# SensorBoard.net
KiCad netlist of a schematic drawn in Altium Designer
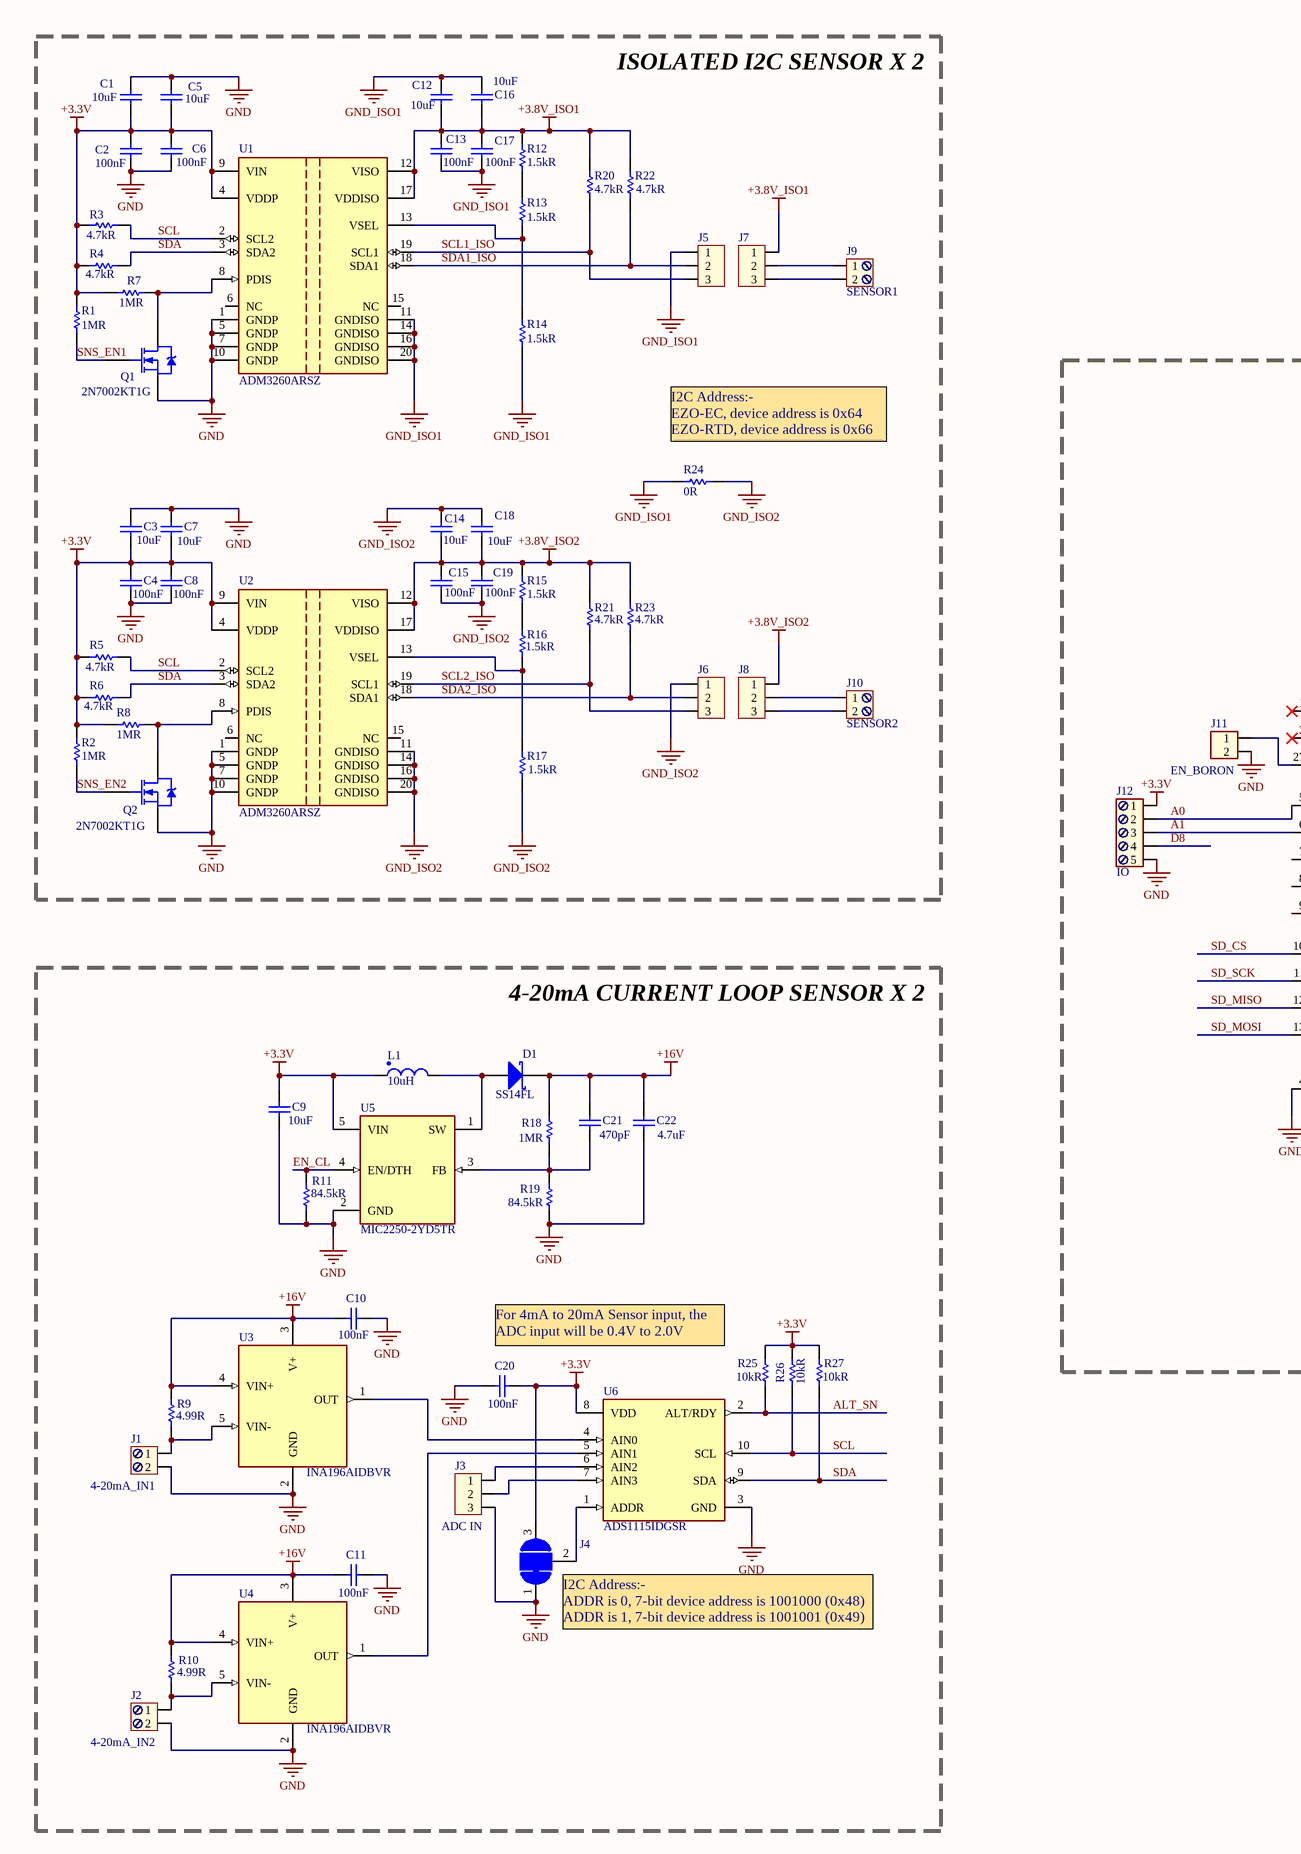
[diagram p0: SensorBoard.SchDoc, left]
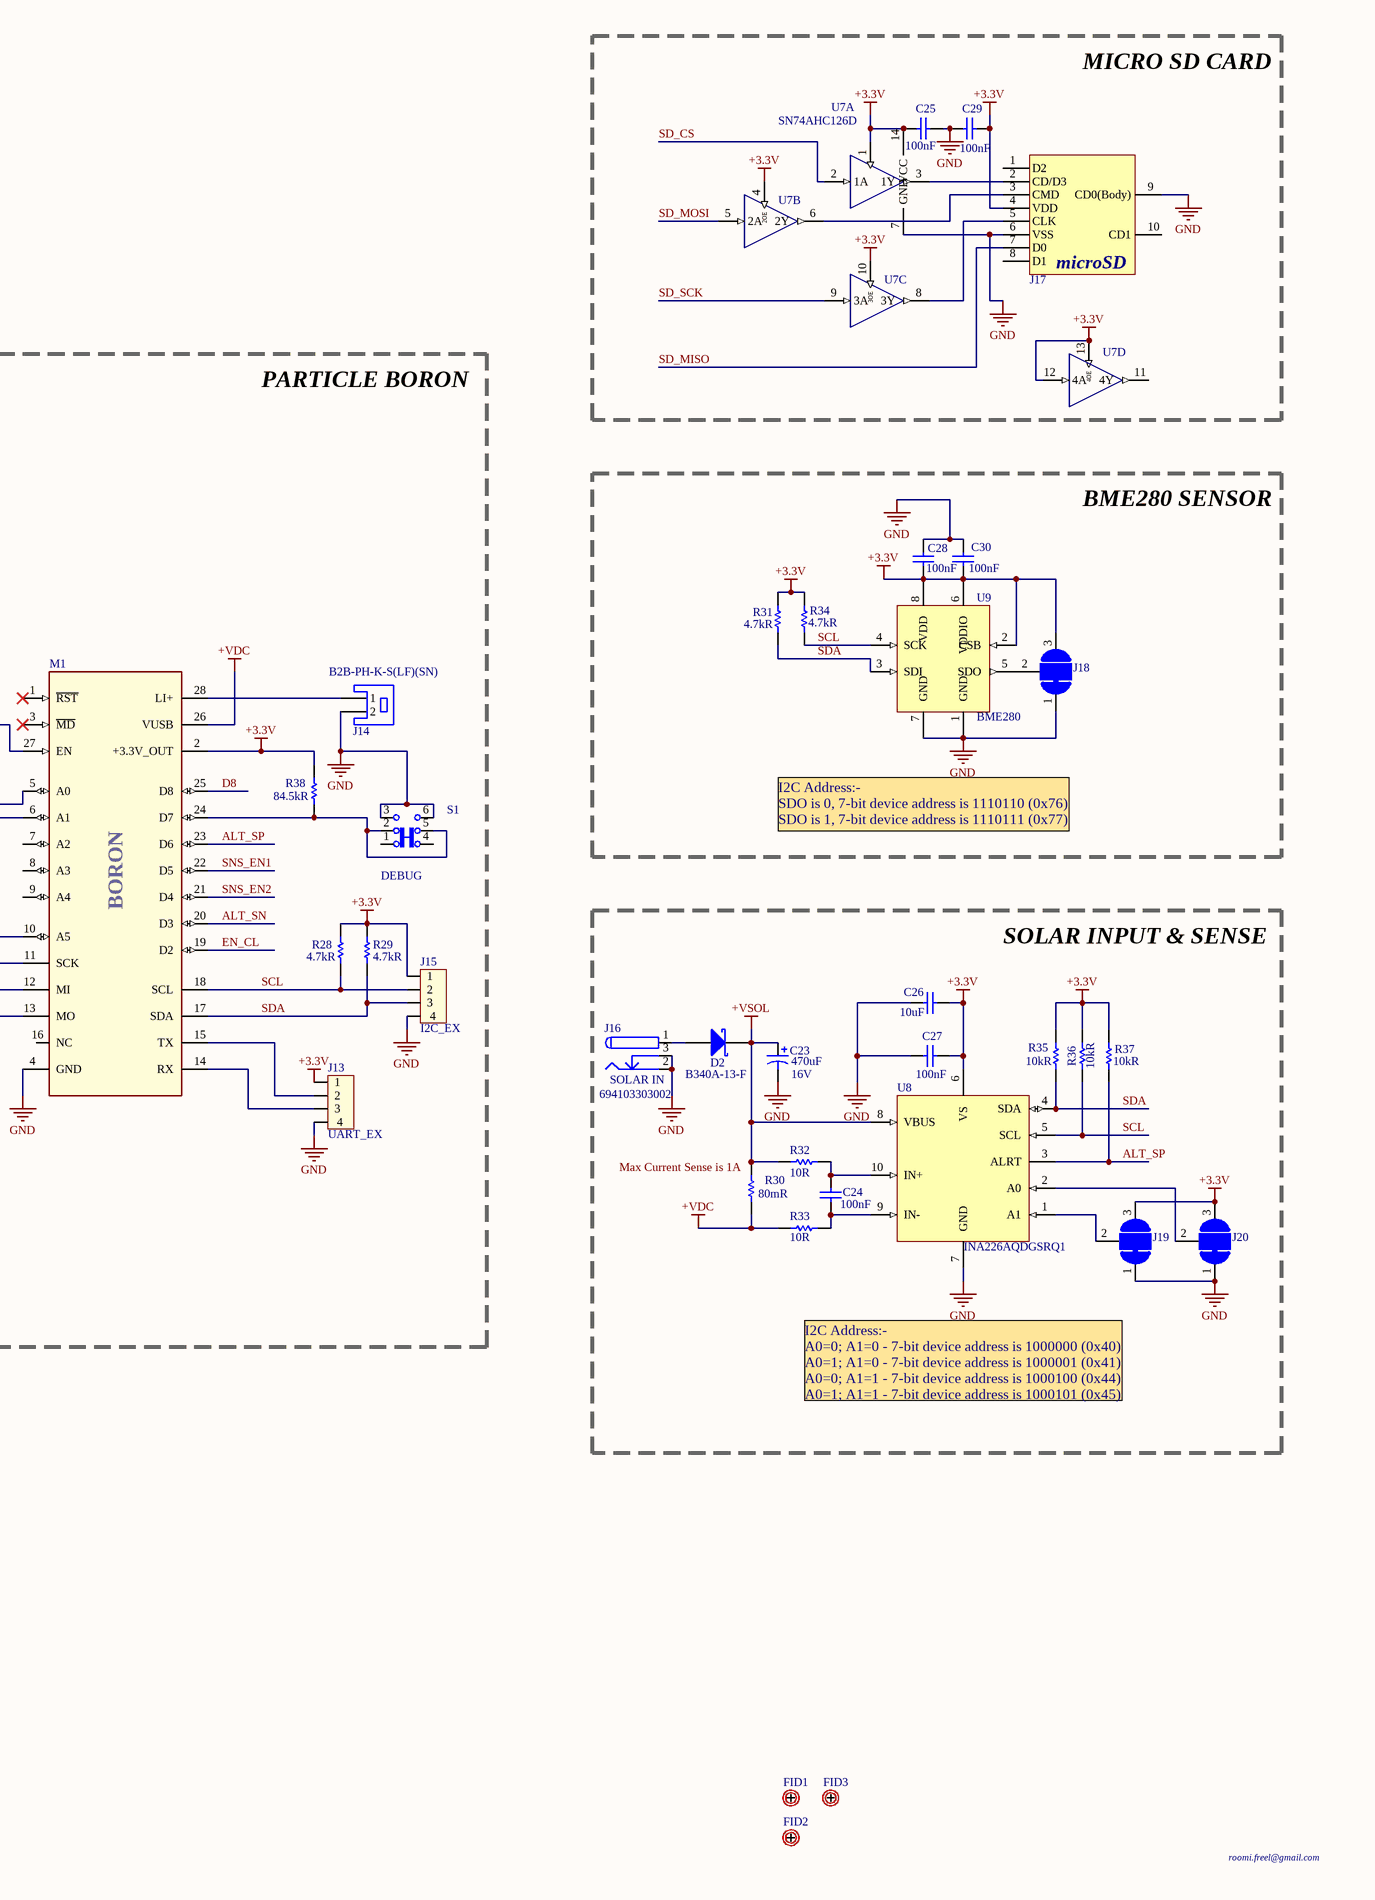
[diagram p1: SensorBoard.SchDoc, right]

(export (version "E")
  (design (tool "Eeschema 10.0.6"))
  (components
    (comp (ref "C1")
      (value "10uF")
      (footprint "C1206")
      (description "Capacitor Non Polar")
      (fields
        (field (name "MANUFACTURER") "Taiyo Yuden")
        (field (name "MANUFACTURER PART NUMBER") "TMK316AB7106KLHT")
        (field (name "CAPACITANCE") "10uF")
      )
      (libsource (lib "RCL_roomi") (part "Capacitor"))
    )
    (comp (ref "C2")
      (value "100nF")
      (footprint "C0805")
      (description "Capacitor Non Polar")
      (fields
        (field (name "MANUFACTURER") "Samsung")
        (field (name "MANUFACTURER PART NUMBER") "CL21B104KCFWPNE")
        (field (name "CAPACITANCE") "100nF")
      )
      (libsource (lib "RCL_roomi") (part "Capacitor"))
    )
    (comp (ref "C3")
      (value "10uF")
      (footprint "C1206")
      (description "Capacitor Non Polar")
      (fields
        (field (name "MANUFACTURER") "Taiyo Yuden")
        (field (name "MANUFACTURER PART NUMBER") "TMK316AB7106KLHT")
        (field (name "CAPACITANCE") "10uF")
      )
      (libsource (lib "RCL_roomi") (part "Capacitor"))
    )
    (comp (ref "C4")
      (value "100nF")
      (footprint "C0805")
      (description "Capacitor Non Polar")
      (fields
        (field (name "MANUFACTURER") "Samsung")
        (field (name "MANUFACTURER PART NUMBER") "CL21B104KCFWPNE")
        (field (name "CAPACITANCE") "100nF")
      )
      (libsource (lib "RCL_roomi") (part "Capacitor"))
    )
    (comp (ref "C5")
      (value "10uF")
      (footprint "C1206")
      (description "Capacitor Non Polar")
      (fields
        (field (name "MANUFACTURER") "Taiyo Yuden")
        (field (name "MANUFACTURER PART NUMBER") "TMK316AB7106KLHT")
        (field (name "CAPACITANCE") "10uF")
      )
      (libsource (lib "RCL_roomi") (part "Capacitor"))
    )
    (comp (ref "C6")
      (value "100nF")
      (footprint "C0805")
      (description "Capacitor Non Polar")
      (fields
        (field (name "MANUFACTURER") "Samsung")
        (field (name "MANUFACTURER PART NUMBER") "CL21B104KCFWPNE")
        (field (name "CAPACITANCE") "100nF")
      )
      (libsource (lib "RCL_roomi") (part "Capacitor"))
    )
    (comp (ref "C7")
      (value "10uF")
      (footprint "C1206")
      (description "Capacitor Non Polar")
      (fields
        (field (name "MANUFACTURER") "Taiyo Yuden")
        (field (name "MANUFACTURER PART NUMBER") "TMK316AB7106KLHT")
        (field (name "CAPACITANCE") "10uF")
      )
      (libsource (lib "RCL_roomi") (part "Capacitor"))
    )
    (comp (ref "C8")
      (value "100nF")
      (footprint "C0805")
      (description "Capacitor Non Polar")
      (fields
        (field (name "MANUFACTURER") "Samsung")
        (field (name "MANUFACTURER PART NUMBER") "CL21B104KCFWPNE")
        (field (name "CAPACITANCE") "100nF")
      )
      (libsource (lib "RCL_roomi") (part "Capacitor"))
    )
    (comp (ref "C9")
      (value "10uF")
      (footprint "C1206")
      (description "Capacitor Non Polar")
      (fields
        (field (name "MANUFACTURER") "Taiyo Yuden")
        (field (name "MANUFACTURER PART NUMBER") "TMK316AB7106KLHT")
        (field (name "CAPACITANCE") "10uF")
      )
      (libsource (lib "RCL_roomi") (part "Capacitor"))
    )
    (comp (ref "C10")
      (value "100nF")
      (footprint "C0805")
      (description "Capacitor Non Polar")
      (fields
        (field (name "MANUFACTURER") "Samsung")
        (field (name "MANUFACTURER PART NUMBER") "CL21B104KCFWPNE")
        (field (name "CAPACITANCE") "100nF")
      )
      (libsource (lib "RCL_roomi") (part "Capacitor"))
    )
    (comp (ref "C11")
      (value "100nF")
      (footprint "C0805")
      (description "Capacitor Non Polar")
      (fields
        (field (name "MANUFACTURER") "Samsung")
        (field (name "MANUFACTURER PART NUMBER") "CL21B104KCFWPNE")
        (field (name "CAPACITANCE") "100nF")
      )
      (libsource (lib "RCL_roomi") (part "Capacitor"))
    )
    (comp (ref "C12")
      (value "10uF")
      (footprint "C1206")
      (description "Capacitor Non Polar")
      (fields
        (field (name "MANUFACTURER") "Taiyo Yuden")
        (field (name "MANUFACTURER PART NUMBER") "TMK316AB7106KLHT")
        (field (name "CAPACITANCE") "10uF")
      )
      (libsource (lib "RCL_roomi") (part "Capacitor"))
    )
    (comp (ref "C13")
      (value "100nF")
      (footprint "C0805")
      (description "Capacitor Non Polar")
      (fields
        (field (name "MANUFACTURER") "Samsung")
        (field (name "MANUFACTURER PART NUMBER") "CL21B104KCFWPNE")
        (field (name "CAPACITANCE") "100nF")
      )
      (libsource (lib "RCL_roomi") (part "Capacitor"))
    )
    (comp (ref "C14")
      (value "10uF")
      (footprint "C1206")
      (description "Capacitor Non Polar")
      (fields
        (field (name "MANUFACTURER") "Taiyo Yuden")
        (field (name "MANUFACTURER PART NUMBER") "TMK316AB7106KLHT")
        (field (name "CAPACITANCE") "10uF")
      )
      (libsource (lib "RCL_roomi") (part "Capacitor"))
    )
    (comp (ref "C15")
      (value "100nF")
      (footprint "C0805")
      (description "Capacitor Non Polar")
      (fields
        (field (name "MANUFACTURER") "Samsung")
        (field (name "MANUFACTURER PART NUMBER") "CL21B104KCFWPNE")
        (field (name "CAPACITANCE") "100nF")
      )
      (libsource (lib "RCL_roomi") (part "Capacitor"))
    )
    (comp (ref "C16")
      (value "10uF")
      (footprint "C1206")
      (description "Capacitor Non Polar")
      (fields
        (field (name "MANUFACTURER") "Taiyo Yuden")
        (field (name "MANUFACTURER PART NUMBER") "TMK316AB7106KLHT")
        (field (name "CAPACITANCE") "10uF")
      )
      (libsource (lib "RCL_roomi") (part "Capacitor"))
    )
    (comp (ref "C17")
      (value "100nF")
      (footprint "C0805")
      (description "Capacitor Non Polar")
      (fields
        (field (name "MANUFACTURER") "Samsung")
        (field (name "MANUFACTURER PART NUMBER") "CL21B104KCFWPNE")
        (field (name "CAPACITANCE") "100nF")
      )
      (libsource (lib "RCL_roomi") (part "Capacitor"))
    )
    (comp (ref "C18")
      (value "10uF")
      (footprint "C1206")
      (description "Capacitor Non Polar")
      (fields
        (field (name "MANUFACTURER") "Taiyo Yuden")
        (field (name "MANUFACTURER PART NUMBER") "TMK316AB7106KLHT")
        (field (name "CAPACITANCE") "10uF")
      )
      (libsource (lib "RCL_roomi") (part "Capacitor"))
    )
    (comp (ref "C19")
      (value "100nF")
      (footprint "C0805")
      (description "Capacitor Non Polar")
      (fields
        (field (name "MANUFACTURER") "Samsung")
        (field (name "MANUFACTURER PART NUMBER") "CL21B104KCFWPNE")
        (field (name "CAPACITANCE") "100nF")
      )
      (libsource (lib "RCL_roomi") (part "Capacitor"))
    )
    (comp (ref "C20")
      (value "100nF")
      (footprint "C0805")
      (description "Capacitor Non Polar")
      (fields
        (field (name "MANUFACTURER") "Samsung")
        (field (name "MANUFACTURER PART NUMBER") "CL21B104KCFWPNE")
        (field (name "CAPACITANCE") "100nF")
      )
      (libsource (lib "RCL_roomi") (part "Capacitor"))
    )
    (comp (ref "C21")
      (value "470pF")
      (footprint "C0805")
      (description "Capacitor Non Polar")
      (fields
        (field (name "MANUFACTURER") "Samsung")
        (field (name "MANUFACTURER PART NUMBER") "CL21B471KC6WPNC")
        (field (name "CAPACITANCE") "470pF")
      )
      (libsource (lib "RCL_roomi") (part "Capacitor"))
    )
    (comp (ref "C22")
      (value "4.7uF")
      (footprint "C1206")
      (description "Capacitor Non Polar")
      (fields
        (field (name "MANUFACTURER") "Murata")
        (field (name "MANUFACTURER PART NUMBER") "GCJ31CR71E475KA12L")
        (field (name "CAPACITANCE") "4.7uF")
      )
      (libsource (lib "RCL_roomi") (part "Capacitor"))
    )
    (comp (ref "C23")
      (value "470uF")
      (footprint "CAPAE120103X102N")
      (description "Capacitor Polar")
      (fields
        (field (name "MANUFACTURER") "Panasonic")
        (field (name "MANUFACTURER PART NUMBER") "EEEHC1C471P")
        (field (name "CAPACITANCE") "470uF")
        (field (name "VOLTAGE RATING (DC)") "16V")
      )
      (libsource (lib "RCL_roomi") (part "Capacitor-Pol"))
    )
    (comp (ref "C24")
      (value "100nF")
      (footprint "C0805")
      (description "Ceramic Chip Capacitor")
      (fields
        (field (name "MANUFACTURER") "Samsung")
        (field (name "MANUFACTURER PART NUMBER") "CL21B104KCFWPNE")
        (field (name "CAPACITANCE") "100nF")
      )
      (libsource (lib "RCL_roomi") (part "Capacitor"))
    )
    (comp (ref "C25")
      (value "100nF")
      (footprint "C0805")
      (description "Capacitor Non Polar")
      (fields
        (field (name "MANUFACTURER") "Samsung")
        (field (name "MANUFACTURER PART NUMBER") "CL21B104KCFWPNE")
        (field (name "CAPACITANCE") "100nF")
      )
      (libsource (lib "RCL_roomi") (part "Capacitor"))
    )
    (comp (ref "C26")
      (value "10uF")
      (footprint "C1206")
      (description "Ceramic Chip Capacitor")
      (fields
        (field (name "MANUFACTURER") "Taiyo Yuden")
        (field (name "MANUFACTURER PART NUMBER") "TMK316AB7106KLHT")
        (field (name "CAPACITANCE") "10uF")
      )
      (libsource (lib "RCL_roomi") (part "Capacitor"))
    )
    (comp (ref "C27")
      (value "100nF")
      (footprint "C0805")
      (description "Ceramic Chip Capacitor")
      (fields
        (field (name "MANUFACTURER") "Samsung")
        (field (name "MANUFACTURER PART NUMBER") "CL21B104KCFWPNE")
        (field (name "CAPACITANCE") "100nF")
      )
      (libsource (lib "RCL_roomi") (part "Capacitor"))
    )
    (comp (ref "C28")
      (value "100nF")
      (footprint "C0805")
      (description "Capacitor Non Polar")
      (fields
        (field (name "MANUFACTURER") "Samsung")
        (field (name "MANUFACTURER PART NUMBER") "CL21B104KCFWPNE")
        (field (name "CAPACITANCE") "100nF")
      )
      (libsource (lib "RCL_roomi") (part "Capacitor"))
    )
    (comp (ref "C29")
      (value "100nF")
      (footprint "C0805")
      (description "Capacitor Non Polar")
      (fields
        (field (name "MANUFACTURER") "Samsung")
        (field (name "MANUFACTURER PART NUMBER") "CL21B104KCFWPNE")
        (field (name "CAPACITANCE") "100nF")
      )
      (libsource (lib "RCL_roomi") (part "Capacitor"))
    )
    (comp (ref "C30")
      (value "100nF")
      (footprint "C0805")
      (description "Capacitor Non Polar")
      (fields
        (field (name "MANUFACTURER") "Samsung")
        (field (name "MANUFACTURER PART NUMBER") "CL21B104KCFWPNE")
        (field (name "CAPACITANCE") "100nF")
      )
      (libsource (lib "RCL_roomi") (part "Capacitor"))
    )
    (comp (ref "D1")
      (value "Diode_Schottky")
      (footprint "SOD-123F")
      (fields
        (field (name "MANUFACTURER") "ON Semiconductor / Fairchild")
        (field (name "MANUFACTURER PART NUMBER") "SS14FL")
      )
      (libsource (lib "Diodes_roomi") (part "Diode_Schottky"))
    )
    (comp (ref "D2")
      (value "Diode_Schottky")
      (footprint "SMA (DO-214AC)")
      (fields
        (field (name "MANUFACTURER") "Diodes")
        (field (name "MANUFACTURER PART NUMBER") "B340A-13-F")
        (field (name "VOLTAGE") "40V")
      )
      (libsource (lib "Diodes_roomi") (part "Diode_Schottky"))
    )
    (comp (ref "FID1")
      (value "Fiducials")
      (footprint "FID_Round")
      (description "Alignment mark for the pick & place machine")
      (libsource (lib "Misc_roomi") (part "Fiducials"))
    )
    (comp (ref "FID2")
      (value "Fiducials")
      (footprint "FID_Round")
      (description "Alignment mark for the pick & place machine")
      (libsource (lib "Misc_roomi") (part "Fiducials"))
    )
    (comp (ref "FID3")
      (value "Fiducials")
      (footprint "FID_Round")
      (description "Alignment mark for the pick & place machine")
      (libsource (lib "Misc_roomi") (part "Fiducials"))
    )
    (comp (ref "J1")
      (value "4-20mA_IN1")
      (footprint "TB-2P-5.08mm")
      (description "Terminal Block 2 position")
      (fields
        (field (name "MANUFACTURER") "Phoenix Contact")
        (field (name "MANUFACTURER PART NUMBER") "1729128")
      )
      (libsource (lib "Con_roomi") (part "TERM_BLK-2P"))
    )
    (comp (ref "J2")
      (value "4-20mA_IN2")
      (footprint "TB-2P-5.08mm")
      (description "Terminal Block 2 position")
      (fields
        (field (name "MANUFACTURER") "Phoenix Contact")
        (field (name "MANUFACTURER PART NUMBER") "1729128")
      )
      (libsource (lib "Con_roomi") (part "TERM_BLK-2P"))
    )
    (comp (ref "J3")
      (value "ADC IN")
      (footprint "TH,POS-3S, 2.54mm")
      (description "HEADER 1X3")
      (libsource (lib "Con_roomi") (part "HDR 1X3"))
    )
    (comp (ref "J4")
      (value "Jumper 3 Pins Normally Closed")
      (footprint "Jumper3P -NC")
      (libsource (lib "Misc_roomi") (part "Jumper-3P_NC"))
    )
    (comp (ref "J5")
      (value "HDR 1X3")
      (footprint "TH,POS-3S,RCPTCL, 2.54mm")
      (description "HEADER 1X3")
      (fields
        (field (name "MANUFACTURER") "Sullins")
        (field (name "MANUFACTURER PART NUMBER") "PPPC031LFBN-RC")
      )
      (libsource (lib "") (part "HDR 1X3_1"))
    )
    (comp (ref "J6")
      (value "HDR 1X3")
      (footprint "TH,POS-3S,RCPTCL, 2.54mm")
      (description "HEADER 1X3")
      (fields
        (field (name "MANUFACTURER") "Sullins")
        (field (name "MANUFACTURER PART NUMBER") "PPPC031LFBN-RC")
      )
      (libsource (lib "") (part "HDR 1X3_1"))
    )
    (comp (ref "J7")
      (value "HDR 1X3")
      (footprint "TH,POS-3S,RCPTCL, 2.54mm")
      (description "HEADER 1X3")
      (fields
        (field (name "MANUFACTURER") "Sullins")
        (field (name "MANUFACTURER PART NUMBER") "PPPC031LFBN-RC")
      )
      (libsource (lib "Con_roomi") (part "HDR 1X3"))
    )
    (comp (ref "J8")
      (value "HDR 1X3")
      (footprint "TH,POS-3S,RCPTCL, 2.54mm")
      (description "HEADER 1X3")
      (fields
        (field (name "MANUFACTURER") "Sullins")
        (field (name "MANUFACTURER PART NUMBER") "PPPC031LFBN-RC")
      )
      (libsource (lib "Con_roomi") (part "HDR 1X3"))
    )
    (comp (ref "J9")
      (value "SENSOR1")
      (footprint "TB-2P-5.08mm")
      (description "Terminal Block 2 position")
      (fields
        (field (name "MANUFACTURER") "Phoenix Contact")
        (field (name "MANUFACTURER PART NUMBER") "1729128")
      )
      (libsource (lib "") (part "TERM_BLK-2P_1"))
    )
    (comp (ref "J10")
      (value "SENSOR2")
      (footprint "TB-2P-5.08mm")
      (description "Terminal Block 2 position")
      (fields
        (field (name "MANUFACTURER") "Phoenix Contact")
        (field (name "MANUFACTURER PART NUMBER") "1729128")
      )
      (libsource (lib "") (part "TERM_BLK-2P_1"))
    )
    (comp (ref "J11")
      (value "EN_BORON")
      (footprint "TH,POS-2S, 2.54mm")
      (description "HEADER 1X2")
      (libsource (lib "Con_roomi") (part "HDR 1X2"))
    )
    (comp (ref "J12")
      (value "IO")
      (footprint "TB-5P-5.08mm")
      (description "Terminal Block 5 position")
      (fields
        (field (name "MANUFACTURER") "Phoenix Contact")
        (field (name "MANUFACTURER PART NUMBER") "1729157")
      )
      (libsource (lib "Con_roomi") (part "TERM_BLK-5P"))
    )
    (comp (ref "J13")
      (value "UART_EX")
      (footprint "TH,POS-4S, 2.54mm")
      (description "HEADER 1X4")
      (libsource (lib "Con_roomi") (part "HDR 1X4"))
    )
    (comp (ref "J14")
      (value "JST-2P")
      (footprint "JST-2P TH V/T 2.0mm")
      (description "JST 2 Pin, Shrouded Connector")
      (fields
        (field (name "MANUFACTURER") "JST")
        (field (name "MANUFACTURER PART NUMBER") "B2B-PH-K-S(LF)(SN)")
      )
      (libsource (lib "Con_roomi") (part "JST-2P"))
    )
    (comp (ref "J15")
      (value "I2C_EX")
      (footprint "TH,POS-4S, 2.54mm")
      (description "HEADER 1X4")
      (libsource (lib "Con_roomi") (part "HDR 1X4"))
    )
    (comp (ref "J16")
      (value "SOLAR IN")
      (footprint "PWR_JACK_1.1x3.5mm")
      (description "DC Barrel Jack Connector Male")
      (fields
        (field (name "MANUFACTURER") "Wurth Electronics")
        (field (name "MANUFACTURER PART NUMBER") "694103303002")
      )
      (libsource (lib "Con_roomi") (part "Barrel Jack"))
    )
    (comp (ref "J17")
      (value "MicroSD")
      (footprint "MicroSD_H-10")
      (description "MicroSD Connector")
      (fields (field (name "MANUFACTURER") "Hirose") (field (name "MANUFACTURER PART NUMBER") "DM3CS-SF"))
      (libsource (lib "Con_roomi") (part "MicroSD"))
    )
    (comp (ref "J18")
      (value "Jumper 3 Pins Normally Closed")
      (footprint "Jumper3P -NC")
      (libsource (lib "") (part "Jumper-3P_NC_1"))
    )
    (comp (ref "J19")
      (value "Jumper 3 Pins Normally Closed")
      (footprint "Jumper3P -NC")
      (libsource (lib "") (part "Jumper-3P_NC_1"))
    )
    (comp (ref "J20")
      (value "Jumper 3 Pins Normally Closed")
      (footprint "Jumper3P -NC")
      (libsource (lib "") (part "Jumper-3P_NC_1"))
    )
    (comp (ref "L1")
      (value "10uH")
      (footprint "INDP5050X40L")
      (description "Generic Inductor")
      (fields
        (field (name "MANUFACTURER") "Taiyo Yuden")
        (field (name "MANUFACTURER PART NUMBER") "NR5040T100M")
        (field (name "INDUCTANCE") "10uH")
      )
      (libsource (lib "RCL_roomi") (part "Inductor"))
    )
    (comp (ref "M1")
      (value "Particle")
      (footprint "Particle Module")
      (description "Particle BORON, ARGON and XENON Module")
      (fields (field (name "MANUFACTURER PART NUMBER") "BORON"))
      (libsource (lib "Modules_Roomi") (part "Particle"))
    )
    (comp (ref "Q1")
      (value "2N7002")
      (footprint "SOT23")
      (description "N-Channel Power MOSFET with Diode")
      (fields
        (field (name "MANUFACTURER") "ON Semiconductor")
        (field (name "MANUFACTURER PART NUMBER") "2N7002KT1G")
      )
      (libsource (lib "Transistors_roomi") (part "MOSFET-N_D"))
    )
    (comp (ref "Q2")
      (value "2N7002")
      (footprint "SOT23")
      (description "N-Channel Power MOSFET with Diode")
      (fields
        (field (name "MANUFACTURER") "ON Semiconductor")
        (field (name "MANUFACTURER PART NUMBER") "2N7002KT1G")
      )
      (libsource (lib "Transistors_roomi") (part "MOSFET-N_D"))
    )
    (comp (ref "R1")
      (value "1MR")
      (footprint "R0805")
      (description "Generic Resistor")
      (fields
        (field (name "MANUFACTURER") "Yageo")
        (field (name "MANUFACTURER PART NUMBER") "AC0805FR-071ML")
        (field (name "RESISTANCE") "1MR")
      )
      (libsource (lib "RCL_roomi") (part "Resistor"))
    )
    (comp (ref "R2")
      (value "1MR")
      (footprint "R0805")
      (description "Generic Resistor")
      (fields
        (field (name "MANUFACTURER") "Yageo")
        (field (name "MANUFACTURER PART NUMBER") "AC0805FR-071ML")
        (field (name "RESISTANCE") "1MR")
      )
      (libsource (lib "RCL_roomi") (part "Resistor"))
    )
    (comp (ref "R3")
      (value "4.7kR")
      (footprint "R0805")
      (description "Generic Resistor")
      (fields
        (field (name "MANUFACTURER") "Yageo")
        (field (name "MANUFACTURER PART NUMBER") "AC0805FR-074K7L")
        (field (name "RESISTANCE") "4.7kR")
      )
      (libsource (lib "RCL_roomi") (part "Resistor"))
    )
    (comp (ref "R4")
      (value "4.7kR")
      (footprint "R0805")
      (description "Generic Resistor")
      (fields
        (field (name "MANUFACTURER") "Yageo")
        (field (name "MANUFACTURER PART NUMBER") "AC0805FR-074K7L")
        (field (name "RESISTANCE") "4.7kR")
      )
      (libsource (lib "RCL_roomi") (part "Resistor"))
    )
    (comp (ref "R5")
      (value "4.7kR")
      (footprint "R0805")
      (description "Generic Resistor")
      (fields
        (field (name "MANUFACTURER") "Yageo")
        (field (name "MANUFACTURER PART NUMBER") "AC0805FR-074K7L")
        (field (name "RESISTANCE") "4.7kR")
      )
      (libsource (lib "RCL_roomi") (part "Resistor"))
    )
    (comp (ref "R6")
      (value "4.7kR")
      (footprint "R0805")
      (description "Generic Resistor")
      (fields
        (field (name "MANUFACTURER") "Yageo")
        (field (name "MANUFACTURER PART NUMBER") "AC0805FR-074K7L")
        (field (name "RESISTANCE") "4.7kR")
      )
      (libsource (lib "RCL_roomi") (part "Resistor"))
    )
    (comp (ref "R7")
      (value "1MR")
      (footprint "R0805")
      (description "Generic Resistor")
      (fields
        (field (name "MANUFACTURER") "Yageo")
        (field (name "MANUFACTURER PART NUMBER") "AC0805FR-071ML")
        (field (name "RESISTANCE") "1MR")
      )
      (libsource (lib "RCL_roomi") (part "Resistor"))
    )
    (comp (ref "R8")
      (value "1MR")
      (footprint "R0805")
      (description "Generic Resistor")
      (fields
        (field (name "MANUFACTURER") "Yageo")
        (field (name "MANUFACTURER PART NUMBER") "AC0805FR-071ML")
        (field (name "RESISTANCE") "1MR")
      )
      (libsource (lib "RCL_roomi") (part "Resistor"))
    )
    (comp (ref "R9")
      (value "4.99R")
      (footprint "R0805")
      (description "Generic Resistor")
      (fields
        (field (name "MANUFACTURER") "Yageo")
        (field (name "MANUFACTURER PART NUMBER") "RC0805FR-074R99L")
        (field (name "RESISTANCE") "4.99R")
      )
      (libsource (lib "RCL_roomi") (part "Resistor"))
    )
    (comp (ref "R10")
      (value "4.99R")
      (footprint "R0805")
      (description "Generic Resistor")
      (fields
        (field (name "MANUFACTURER") "Yageo")
        (field (name "MANUFACTURER PART NUMBER") "RC0805FR-074R99L")
        (field (name "RESISTANCE") "4.99R")
      )
      (libsource (lib "RCL_roomi") (part "Resistor"))
    )
    (comp (ref "R11")
      (value "84.5kR")
      (footprint "R0805")
      (description "Generic Resistor")
      (fields
        (field (name "MANUFACTURER") "Vishay")
        (field (name "MANUFACTURER PART NUMBER") "CRCW080584K5FKEA")
        (field (name "RESISTANCE") "84.5kR")
      )
      (libsource (lib "RCL_roomi") (part "Resistor"))
    )
    (comp (ref "R12")
      (value "1.5kR")
      (footprint "R0805")
      (description "Generic Resistor")
      (fields
        (field (name "MANUFACTURER") "Yageo")
        (field (name "MANUFACTURER PART NUMBER") "AC0805FR-071K5L")
        (field (name "RESISTANCE") "1.5kR")
      )
      (libsource (lib "RCL_roomi") (part "Resistor"))
    )
    (comp (ref "R13")
      (value "1.5kR")
      (footprint "R0805")
      (description "Generic Resistor")
      (fields
        (field (name "MANUFACTURER") "Yageo")
        (field (name "MANUFACTURER PART NUMBER") "AC0805FR-071K5L")
        (field (name "RESISTANCE") "1.5kR")
      )
      (libsource (lib "RCL_roomi") (part "Resistor"))
    )
    (comp (ref "R14")
      (value "1.5kR")
      (footprint "R0805")
      (description "Generic Resistor")
      (fields
        (field (name "MANUFACTURER") "Yageo")
        (field (name "MANUFACTURER PART NUMBER") "AC0805FR-071K5L")
        (field (name "RESISTANCE") "1.5kR")
      )
      (libsource (lib "RCL_roomi") (part "Resistor"))
    )
    (comp (ref "R15")
      (value "1.5kR")
      (footprint "R0805")
      (description "Generic Resistor")
      (fields
        (field (name "MANUFACTURER") "Yageo")
        (field (name "MANUFACTURER PART NUMBER") "AC0805FR-071K5L")
        (field (name "RESISTANCE") "1.5kR")
      )
      (libsource (lib "RCL_roomi") (part "Resistor"))
    )
    (comp (ref "R16")
      (value "1.5kR")
      (footprint "R0805")
      (description "Generic Resistor")
      (fields
        (field (name "MANUFACTURER") "Yageo")
        (field (name "MANUFACTURER PART NUMBER") "AC0805FR-071K5L")
        (field (name "RESISTANCE") "1.5kR")
      )
      (libsource (lib "RCL_roomi") (part "Resistor"))
    )
    (comp (ref "R17")
      (value "1.5kR")
      (footprint "R0805")
      (description "Generic Resistor")
      (fields
        (field (name "MANUFACTURER") "Yageo")
        (field (name "MANUFACTURER PART NUMBER") "AC0805FR-071K5L")
        (field (name "RESISTANCE") "1.5kR")
      )
      (libsource (lib "RCL_roomi") (part "Resistor"))
    )
    (comp (ref "R18")
      (value "1MR")
      (footprint "R0805")
      (description "Generic Resistor")
      (fields
        (field (name "MANUFACTURER") "Yageo")
        (field (name "MANUFACTURER PART NUMBER") "AC0805FR-071ML")
        (field (name "RESISTANCE") "1MR")
      )
      (libsource (lib "RCL_roomi") (part "Resistor"))
    )
    (comp (ref "R19")
      (value "84.5kR")
      (footprint "R0805")
      (description "Generic Resistor")
      (fields
        (field (name "MANUFACTURER") "Vishay")
        (field (name "MANUFACTURER PART NUMBER") "CRCW080584K5FKEA")
        (field (name "RESISTANCE") "84.5kR")
      )
      (libsource (lib "RCL_roomi") (part "Resistor"))
    )
    (comp (ref "R20")
      (value "4.7kR")
      (footprint "R0805")
      (description "Generic Resistor")
      (fields
        (field (name "MANUFACTURER") "Yageo")
        (field (name "MANUFACTURER PART NUMBER") "AC0805FR-074K7L")
        (field (name "RESISTANCE") "4.7kR")
      )
      (libsource (lib "RCL_roomi") (part "Resistor"))
    )
    (comp (ref "R21")
      (value "4.7kR")
      (footprint "R0805")
      (description "Generic Resistor")
      (fields
        (field (name "MANUFACTURER") "Yageo")
        (field (name "MANUFACTURER PART NUMBER") "AC0805FR-074K7L")
        (field (name "RESISTANCE") "4.7kR")
      )
      (libsource (lib "RCL_roomi") (part "Resistor"))
    )
    (comp (ref "R22")
      (value "4.7kR")
      (footprint "R0805")
      (description "Generic Resistor")
      (fields
        (field (name "MANUFACTURER") "Yageo")
        (field (name "MANUFACTURER PART NUMBER") "AC0805FR-074K7L")
        (field (name "RESISTANCE") "4.7kR")
      )
      (libsource (lib "RCL_roomi") (part "Resistor"))
    )
    (comp (ref "R23")
      (value "4.7kR")
      (footprint "R0805")
      (description "Generic Resistor")
      (fields
        (field (name "MANUFACTURER") "Yageo")
        (field (name "MANUFACTURER PART NUMBER") "AC0805FR-074K7L")
        (field (name "RESISTANCE") "4.7kR")
      )
      (libsource (lib "RCL_roomi") (part "Resistor"))
    )
    (comp (ref "R24")
      (value "0R")
      (footprint "R0805")
      (description "Generic Resistor")
      (fields (field (name "Comment") "DNP") (field (name "PUBLISHER") "Altium Limited"))
      (libsource (lib "RCL_roomi") (part "Resistor"))
    )
    (comp (ref "R25")
      (value "10kR")
      (footprint "R0805")
      (description "Generic Resistor")
      (fields
        (field (name "MANUFACTURER") "Yageo")
        (field (name "MANUFACTURER PART NUMBER") "AC0805FR-0710KL")
        (field (name "RESISTANCE") "10kR")
      )
      (libsource (lib "RCL_roomi") (part "Resistor"))
    )
    (comp (ref "R26")
      (value "10kR")
      (footprint "R0805")
      (description "Generic Resistor")
      (fields
        (field (name "MANUFACTURER") "Yageo")
        (field (name "MANUFACTURER PART NUMBER") "AC0805FR-0710KL")
        (field (name "RESISTANCE") "10kR")
      )
      (libsource (lib "RCL_roomi") (part "Resistor"))
    )
    (comp (ref "R27")
      (value "10kR")
      (footprint "R0805")
      (description "Generic Resistor")
      (fields
        (field (name "MANUFACTURER") "Yageo")
        (field (name "MANUFACTURER PART NUMBER") "AC0805FR-0710KL")
        (field (name "RESISTANCE") "10kR")
      )
      (libsource (lib "RCL_roomi") (part "Resistor"))
    )
    (comp (ref "R28")
      (value "4.7kR")
      (footprint "R0805")
      (description "Generic Resistor")
      (fields
        (field (name "MANUFACTURER") "Yageo")
        (field (name "MANUFACTURER PART NUMBER") "AC0805FR-074K7L")
        (field (name "RESISTANCE") "4.7kR")
      )
      (libsource (lib "RCL_roomi") (part "Resistor"))
    )
    (comp (ref "R29")
      (value "4.7kR")
      (footprint "R0805")
      (description "Generic Resistor")
      (fields
        (field (name "MANUFACTURER") "Yageo")
        (field (name "MANUFACTURER PART NUMBER") "AC0805FR-074K7L")
        (field (name "RESISTANCE") "4.7kR")
      )
      (libsource (lib "RCL_roomi") (part "Resistor"))
    )
    (comp (ref "R30")
      (value "80mR")
      (footprint "R2512")
      (description "Generic Resistor")
      (fields
        (field (name "MANUFACTURER") "Bourns")
        (field (name "MANUFACTURER PART NUMBER") "CRA2512-FZ-R080ELF")
        (field (name "RESISTANCE") "80mR")
      )
      (libsource (lib "RCL_roomi") (part "Resistor"))
    )
    (comp (ref "R31")
      (value "4.7kR")
      (footprint "R0805")
      (description "Generic Resistor")
      (fields
        (field (name "MANUFACTURER") "Yageo")
        (field (name "MANUFACTURER PART NUMBER") "AC0805FR-074K7L")
        (field (name "RESISTANCE") "4.7kR")
      )
      (libsource (lib "RCL_roomi") (part "Resistor"))
    )
    (comp (ref "R32")
      (value "10R")
      (footprint "R0805")
      (description "Generic Resistor")
      (fields
        (field (name "MANUFACTURER") "Yageo")
        (field (name "MANUFACTURER PART NUMBER") "AC0805FR-0710RL")
        (field (name "RESISTANCE") "10R")
      )
      (libsource (lib "RCL_roomi") (part "Resistor"))
    )
    (comp (ref "R33")
      (value "10R")
      (footprint "R0805")
      (description "Generic Resistor")
      (fields
        (field (name "MANUFACTURER") "Yageo")
        (field (name "MANUFACTURER PART NUMBER") "AC0805FR-0710RL")
        (field (name "RESISTANCE") "10R")
      )
      (libsource (lib "RCL_roomi") (part "Resistor"))
    )
    (comp (ref "R34")
      (value "4.7kR")
      (footprint "R0805")
      (description "Generic Resistor")
      (fields
        (field (name "MANUFACTURER") "Yageo")
        (field (name "MANUFACTURER PART NUMBER") "AC0805FR-074K7L")
        (field (name "RESISTANCE") "4.7kR")
      )
      (libsource (lib "RCL_roomi") (part "Resistor"))
    )
    (comp (ref "R35")
      (value "10kR")
      (footprint "R0805")
      (description "Generic Resistor")
      (fields
        (field (name "MANUFACTURER") "Yageo")
        (field (name "MANUFACTURER PART NUMBER") "AC0805FR-0710KL")
        (field (name "RESISTANCE") "10kR")
      )
      (libsource (lib "RCL_roomi") (part "Resistor"))
    )
    (comp (ref "R36")
      (value "10kR")
      (footprint "R0805")
      (description "Generic Resistor")
      (fields
        (field (name "MANUFACTURER") "Yageo")
        (field (name "MANUFACTURER PART NUMBER") "AC0805FR-0710KL")
        (field (name "RESISTANCE") "10kR")
      )
      (libsource (lib "RCL_roomi") (part "Resistor"))
    )
    (comp (ref "R37")
      (value "10kR")
      (footprint "R0805")
      (description "Generic Resistor")
      (fields
        (field (name "MANUFACTURER") "Yageo")
        (field (name "MANUFACTURER PART NUMBER") "AC0805FR-0710KL")
        (field (name "RESISTANCE") "10kR")
      )
      (libsource (lib "RCL_roomi") (part "Resistor"))
    )
    (comp (ref "R38")
      (value "84.5kR")
      (footprint "R0805")
      (description "Generic Resistor")
      (fields
        (field (name "MANUFACTURER") "Vishay")
        (field (name "MANUFACTURER PART NUMBER") "CRCW080584K5FKEA")
        (field (name "RESISTANCE") "84.5kR")
      )
      (libsource (lib "RCL_roomi") (part "Resistor"))
    )
    (comp (ref "S1")
      (value "DEBUG")
      (footprint "Slide_DPDT_TH1")
      (description "Slide Switch DPDT")
      (fields (field (name "MANUFACTURER") "ITT C&K") (field (name "MANUFACTURER PART NUMBER") "JS202011CQN"))
      (libsource (lib "Switches_roomi") (part "Slide_DPDT"))
    )
    (comp (ref "U1")
      (value "ADM3260ARSZ")
      (footprint "SSOP-20")
      (fields
        (field (name "MANUFACTURER") "Analog Devices")
        (field (name "MANUFACTURER PART NUMBER") "ADM3260ARSZ")
      )
      (libsource (lib "IC_roomi") (part "ADM3260ARSZ"))
    )
    (comp (ref "U2")
      (value "ADM3260ARSZ")
      (footprint "SSOP-20")
      (fields
        (field (name "MANUFACTURER") "Analog Devices")
        (field (name "MANUFACTURER PART NUMBER") "ADM3260ARSZ")
      )
      (libsource (lib "IC_roomi") (part "ADM3260ARSZ"))
    )
    (comp (ref "U3")
      (value "INA196AIDBVR")
      (footprint "SOT23-5")
      (description "IC CURRENT MONITOR 3% SOT23-5")
      (fields
        (field (name "MANUFACTURER") "Texas Instruments")
        (field (name "MANUFACTURER PART NUMBER") "INA196AIDBVR")
      )
      (libsource (lib "IC_roomi") (part "INA196AIDBVR"))
    )
    (comp (ref "U4")
      (value "INA196AIDBVR")
      (footprint "SOT23-5")
      (description "IC CURRENT MONITOR 3% SOT23-5")
      (fields
        (field (name "MANUFACTURER") "Texas Instruments")
        (field (name "MANUFACTURER PART NUMBER") "INA196AIDBVR")
      )
      (libsource (lib "IC_roomi") (part "INA196AIDBVR"))
    )
    (comp (ref "U5")
      (value "MIC2250-2YD5TR")
      (footprint "SOT23-5")
      (description "Conv DC-DC Single Step Up 2.5V to 5.5V 5-Pin TSOT-23 T/R")
      (fields
        (field (name "MANUFACTURER") "Microchip Micrel")
        (field (name "MANUFACTURER PART NUMBER") "MIC2250-2YD5TR")
      )
      (libsource (lib "IC_roomi") (part "MIC2250-2YD5TR"))
    )
    (comp (ref "U6")
      (value "ADS1115IDGSR")
      (footprint "VSSOP-10")
      (description "IC ADC 16BIT 860SPS LP 10MSOP")
      (fields
        (field (name "MANUFACTURER") "Texas Instruments")
        (field (name "MANUFACTURER PART NUMBER") "ADS1115IDGSR")
      )
      (libsource (lib "IC_roomi") (part "ADS1115IDGSR"))
    )
    (comp (ref "U7")
      (value "SN74AHC126D")
      (footprint "SOIC-14")
      (description "IC BUS BUFFER TRI-ST QD 14SOIC")
      (fields
        (field (name "MANUFACTURER") "Texas Instruments")
        (field (name "MANUFACTURER PART NUMBER") "SN74AHC126D")
      )
      (libsource (lib "IC_roomi") (part "SN74AHC126D"))
    )
    (comp (ref "U8")
      (value "INA226AQDGSRQ1")
      (footprint "MSOP-10")
      (description "IC MONITOR PWR/CURR BIDIR 10MSOP")
      (fields
        (field (name "MANUFACTURER") "Texas Instruments")
        (field (name "MANUFACTURER PART NUMBER") "INA226AQDGSRQ1")
      )
      (libsource (lib "IC_roomi") (part "INA226AQDGSRQ1"))
    )
    (comp (ref "U9")
      (value "BME280")
      (footprint "LGA-8 -1")
      (description "PRESSURE HUMIDITY TEMP GAS SENS")
      (fields
        (field (name "MANUFACTURER") "Bosch Sensortec")
        (field (name "MANUFACTURER PART NUMBER") "BME280")
      )
      (libsource (lib "IC_roomi") (part "BME280"))
    )
  )
  (nets
    (net (code "1") (name "+3.3V") (class "Default")
      (node (ref "C1") (pin "2") (pinfunction "2_2") (pintype "passive"))
      (node (ref "C2") (pin "1") (pinfunction "1_1") (pintype "passive"))
      (node (ref "C20") (pin "2") (pinfunction "2_2") (pintype "passive"))
      (node (ref "C25") (pin "2") (pinfunction "2_2") (pintype "passive"))
      (node (ref "C26") (pin "1") (pinfunction "1_1") (pintype "passive"))
      (node (ref "C27") (pin "1") (pinfunction "1_1") (pintype "passive"))
      (node (ref "C28") (pin "2") (pinfunction "2_2") (pintype "passive"))
      (node (ref "C29") (pin "1") (pinfunction "1_1") (pintype "passive"))
      (node (ref "C3") (pin "2") (pinfunction "2_2") (pintype "passive"))
      (node (ref "C30") (pin "2") (pinfunction "2_2") (pintype "passive"))
      (node (ref "C4") (pin "1") (pinfunction "1_1") (pintype "passive"))
      (node (ref "C5") (pin "2") (pinfunction "2_2") (pintype "passive"))
      (node (ref "C6") (pin "1") (pinfunction "1_1") (pintype "passive"))
      (node (ref "C7") (pin "2") (pinfunction "2_2") (pintype "passive"))
      (node (ref "C8") (pin "1") (pinfunction "1_1") (pintype "passive"))
      (node (ref "C9") (pin "2") (pinfunction "2_2") (pintype "passive"))
      (node (ref "J12") (pin "1") (pinfunction "1_1") (pintype "passive"))
      (node (ref "J13") (pin "1") (pinfunction "1_1") (pintype "passive"))
      (node (ref "J15") (pin "1") (pinfunction "1_1") (pintype "passive"))
      (node (ref "J17") (pin "4") (pinfunction "VDD_4") (pintype "passive"))
      (node (ref "J18") (pin "3") (pinfunction "3_3") (pintype "passive"))
      (node (ref "J19") (pin "3") (pinfunction "3_3") (pintype "passive"))
      (node (ref "J20") (pin "3") (pinfunction "3_3") (pintype "passive"))
      (node (ref "J4") (pin "3") (pinfunction "3_3") (pintype "passive"))
      (node (ref "L1") (pin "1") (pinfunction "1_1") (pintype "passive"))
      (node (ref "M1") (pin "2") (pinfunction "+3.3V_OUT_2") (pintype "power_in"))
      (node (ref "R1") (pin "2") (pinfunction "2_2") (pintype "passive"))
      (node (ref "R2") (pin "2") (pinfunction "2_2") (pintype "passive"))
      (node (ref "R25") (pin "2") (pinfunction "2_2") (pintype "passive"))
      (node (ref "R26") (pin "2") (pinfunction "2_2") (pintype "passive"))
      (node (ref "R27") (pin "2") (pinfunction "2_2") (pintype "passive"))
      (node (ref "R28") (pin "2") (pinfunction "2_2") (pintype "passive"))
      (node (ref "R29") (pin "2") (pinfunction "2_2") (pintype "passive"))
      (node (ref "R3") (pin "2") (pinfunction "2_2") (pintype "passive"))
      (node (ref "R31") (pin "2") (pinfunction "2_2") (pintype "passive"))
      (node (ref "R34") (pin "2") (pinfunction "2_2") (pintype "passive"))
      (node (ref "R35") (pin "2") (pinfunction "2_2") (pintype "passive"))
      (node (ref "R36") (pin "2") (pinfunction "2_2") (pintype "passive"))
      (node (ref "R37") (pin "2") (pinfunction "2_2") (pintype "passive"))
      (node (ref "R38") (pin "2") (pinfunction "2_2") (pintype "passive"))
      (node (ref "R4") (pin "2") (pinfunction "2_2") (pintype "passive"))
      (node (ref "R5") (pin "2") (pinfunction "2_2") (pintype "passive"))
      (node (ref "R6") (pin "2") (pinfunction "2_2") (pintype "passive"))
      (node (ref "R7") (pin "2") (pinfunction "2_2") (pintype "passive"))
      (node (ref "R8") (pin "2") (pinfunction "2_2") (pintype "passive"))
      (node (ref "U1") (pin "4") (pinfunction "VDDP_4") (pintype "power_in"))
      (node (ref "U1") (pin "9") (pinfunction "VIN_9") (pintype "power_in"))
      (node (ref "U2") (pin "4") (pinfunction "VDDP_4") (pintype "power_in"))
      (node (ref "U2") (pin "9") (pinfunction "VIN_9") (pintype "power_in"))
      (node (ref "U5") (pin "5") (pinfunction "VIN_5") (pintype "power_in"))
      (node (ref "U6") (pin "8") (pinfunction "VDD_8") (pintype "power_in"))
      (node (ref "U7") (pin "1") (pinfunction "1OE_1") (pintype "input"))
      (node (ref "U7") (pin "10") (pinfunction "3OE_10") (pintype "input"))
      (node (ref "U7") (pin "12") (pinfunction "4A_12") (pintype "input"))
      (node (ref "U7") (pin "13") (pinfunction "4OE_13") (pintype "input"))
      (node (ref "U7") (pin "14") (pinfunction "VCC_14") (pintype "power_in"))
      (node (ref "U7") (pin "4") (pinfunction "2OE_4") (pintype "input"))
      (node (ref "U8") (pin "6") (pinfunction "VS_6") (pintype "power_in"))
      (node (ref "U9") (pin "2") (pinfunction "CSB_2") (pintype "input"))
      (node (ref "U9") (pin "6") (pinfunction "VDDIO_6") (pintype "power_in"))
      (node (ref "U9") (pin "8") (pinfunction "VDD_8") (pintype "power_in"))
    )
    (net (code "2") (name "+3.8V_ISO1") (class "Default")
      (node (ref "C12") (pin "2") (pinfunction "2_2") (pintype "passive"))
      (node (ref "C13") (pin "1") (pinfunction "1_1") (pintype "passive"))
      (node (ref "C16") (pin "2") (pinfunction "2_2") (pintype "passive"))
      (node (ref "C17") (pin "1") (pinfunction "1_1") (pintype "passive"))
      (node (ref "J7") (pin "1") (pinfunction "1_1") (pintype "passive"))
      (node (ref "R12") (pin "2") (pinfunction "2_2") (pintype "passive"))
      (node (ref "R20") (pin "2") (pinfunction "2_2") (pintype "passive"))
      (node (ref "R22") (pin "2") (pinfunction "2_2") (pintype "passive"))
      (node (ref "U1") (pin "12") (pinfunction "VISO_12") (pintype "power_in"))
      (node (ref "U1") (pin "17") (pinfunction "VDDISO_17") (pintype "power_in"))
    )
    (net (code "3") (name "+3.8V_ISO2") (class "Default")
      (node (ref "C14") (pin "2") (pinfunction "2_2") (pintype "passive"))
      (node (ref "C15") (pin "1") (pinfunction "1_1") (pintype "passive"))
      (node (ref "C18") (pin "2") (pinfunction "2_2") (pintype "passive"))
      (node (ref "C19") (pin "1") (pinfunction "1_1") (pintype "passive"))
      (node (ref "J8") (pin "1") (pinfunction "1_1") (pintype "passive"))
      (node (ref "R15") (pin "2") (pinfunction "2_2") (pintype "passive"))
      (node (ref "R21") (pin "2") (pinfunction "2_2") (pintype "passive"))
      (node (ref "R23") (pin "2") (pinfunction "2_2") (pintype "passive"))
      (node (ref "U2") (pin "12") (pinfunction "VISO_12") (pintype "power_in"))
      (node (ref "U2") (pin "17") (pinfunction "VDDISO_17") (pintype "power_in"))
    )
    (net (code "4") (name "+16V") (class "Default")
      (node (ref "C10") (pin "1") (pinfunction "1_1") (pintype "passive"))
      (node (ref "C11") (pin "1") (pinfunction "1_1") (pintype "passive"))
      (node (ref "C21") (pin "2") (pinfunction "2_2") (pintype "passive"))
      (node (ref "C22") (pin "2") (pinfunction "2_2") (pintype "passive"))
      (node (ref "D1") (pin "2") (pinfunction "K_2") (pintype "passive"))
      (node (ref "R10") (pin "2") (pinfunction "2_2") (pintype "passive"))
      (node (ref "R18") (pin "2") (pinfunction "2_2") (pintype "passive"))
      (node (ref "R9") (pin "2") (pinfunction "2_2") (pintype "passive"))
      (node (ref "U3") (pin "3") (pinfunction "V+_3") (pintype "power_in"))
      (node (ref "U3") (pin "4") (pinfunction "VIN+_4") (pintype "input"))
      (node (ref "U4") (pin "3") (pinfunction "V+_3") (pintype "power_in"))
      (node (ref "U4") (pin "4") (pinfunction "VIN+_4") (pintype "input"))
    )
    (net (code "5") (name "+VDC") (class "Default")
      (node (ref "M1") (pin "26") (pinfunction "VUSB_26") (pintype "power_in"))
      (node (ref "R30") (pin "1") (pinfunction "1_1") (pintype "passive"))
      (node (ref "R33") (pin "2") (pinfunction "2_2") (pintype "passive"))
    )
    (net (code "6") (name "+VSOL") (class "Default")
      (node (ref "C23") (pin "1") (pinfunction "1_1") (pintype "passive"))
      (node (ref "D2") (pin "2") (pinfunction "K_2") (pintype "passive"))
      (node (ref "R30") (pin "2") (pinfunction "2_2") (pintype "passive"))
      (node (ref "R32") (pin "2") (pinfunction "2_2") (pintype "passive"))
      (node (ref "U8") (pin "8") (pinfunction "VBUS_8") (pintype "input"))
    )
    (net (code "7") (name "/A0") (class "Default")
      (node (ref "J12") (pin "2") (pinfunction "2_2") (pintype "passive"))
      (node (ref "M1") (pin "5") (pinfunction "A0_5") (pintype "bidirectional"))
    )
    (net (code "8") (name "/A1") (class "Default")
      (node (ref "J12") (pin "3") (pinfunction "3_3") (pintype "passive"))
      (node (ref "M1") (pin "6") (pinfunction "A1_6") (pintype "bidirectional"))
    )
    (net (code "9") (name "/ALT_SN") (class "Default")
      (node (ref "M1") (pin "20") (pinfunction "D3_20") (pintype "bidirectional"))
      (node (ref "R25") (pin "1") (pinfunction "1_1") (pintype "passive"))
      (node (ref "U6") (pin "2") (pinfunction "ALT/RDY_2") (pintype "output"))
    )
    (net (code "10") (name "/ALT_SP") (class "Default")
      (node (ref "M1") (pin "23") (pinfunction "D6_23") (pintype "bidirectional"))
      (node (ref "R37") (pin "1") (pinfunction "1_1") (pintype "passive"))
      (node (ref "U8") (pin "3") (pinfunction "ALRT_3") (pintype "open_collector"))
    )
    (net (code "11") (name "/D8") (class "Default")
      (node (ref "J12") (pin "4") (pinfunction "4_4") (pintype "passive"))
      (node (ref "M1") (pin "25") (pinfunction "D8_25") (pintype "bidirectional"))
    )
    (net (code "12") (name "/EN_CL") (class "Default")
      (node (ref "M1") (pin "19") (pinfunction "D2_19") (pintype "bidirectional"))
      (node (ref "R11") (pin "2") (pinfunction "2_2") (pintype "passive"))
      (node (ref "U5") (pin "4") (pinfunction "EN/DTH_4") (pintype "input"))
    )
    (net (code "13") (name "/SCL") (class "Default")
      (node (ref "J15") (pin "2") (pinfunction "2_2") (pintype "passive"))
      (node (ref "M1") (pin "18") (pinfunction "SCL_18") (pintype "passive"))
      (node (ref "R26") (pin "1") (pinfunction "1_1") (pintype "passive"))
      (node (ref "R28") (pin "1") (pinfunction "1_1") (pintype "passive"))
      (node (ref "R3") (pin "1") (pinfunction "1_1") (pintype "passive"))
      (node (ref "R34") (pin "1") (pinfunction "1_1") (pintype "passive"))
      (node (ref "R36") (pin "1") (pinfunction "1_1") (pintype "passive"))
      (node (ref "R5") (pin "1") (pinfunction "1_1") (pintype "passive"))
      (node (ref "U1") (pin "2") (pinfunction "SCL2_2") (pintype "bidirectional"))
      (node (ref "U2") (pin "2") (pinfunction "SCL2_2") (pintype "bidirectional"))
      (node (ref "U6") (pin "10") (pinfunction "SCL_10") (pintype "input"))
      (node (ref "U8") (pin "5") (pinfunction "SCL_5") (pintype "input"))
      (node (ref "U9") (pin "4") (pinfunction "SCK_4") (pintype "input"))
    )
    (net (code "14") (name "/SCL1_ISO") (class "Default")
      (node (ref "J5") (pin "3") (pinfunction "3_3") (pintype "passive"))
      (node (ref "R20") (pin "1") (pinfunction "1_1") (pintype "passive"))
      (node (ref "U1") (pin "19") (pinfunction "SCL1_19") (pintype "bidirectional"))
    )
    (net (code "15") (name "/SCL2_ISO") (class "Default")
      (node (ref "J6") (pin "3") (pinfunction "3_3") (pintype "passive"))
      (node (ref "R21") (pin "1") (pinfunction "1_1") (pintype "passive"))
      (node (ref "U2") (pin "19") (pinfunction "SCL1_19") (pintype "bidirectional"))
    )
    (net (code "16") (name "/SDA") (class "Default")
      (node (ref "J15") (pin "3") (pinfunction "3_3") (pintype "passive"))
      (node (ref "M1") (pin "17") (pinfunction "SDA_17") (pintype "passive"))
      (node (ref "R27") (pin "1") (pinfunction "1_1") (pintype "passive"))
      (node (ref "R29") (pin "1") (pinfunction "1_1") (pintype "passive"))
      (node (ref "R31") (pin "1") (pinfunction "1_1") (pintype "passive"))
      (node (ref "R35") (pin "1") (pinfunction "1_1") (pintype "passive"))
      (node (ref "R4") (pin "1") (pinfunction "1_1") (pintype "passive"))
      (node (ref "R6") (pin "1") (pinfunction "1_1") (pintype "passive"))
      (node (ref "U1") (pin "3") (pinfunction "SDA2_3") (pintype "bidirectional"))
      (node (ref "U2") (pin "3") (pinfunction "SDA2_3") (pintype "bidirectional"))
      (node (ref "U6") (pin "9") (pinfunction "SDA_9") (pintype "bidirectional"))
      (node (ref "U8") (pin "4") (pinfunction "SDA_4") (pintype "bidirectional"))
      (node (ref "U9") (pin "3") (pinfunction "SDI_3") (pintype "input"))
    )
    (net (code "17") (name "/SDA1_ISO") (class "Default")
      (node (ref "J5") (pin "2") (pinfunction "2_2") (pintype "passive"))
      (node (ref "R22") (pin "1") (pinfunction "1_1") (pintype "passive"))
      (node (ref "U1") (pin "18") (pinfunction "SDA1_18") (pintype "bidirectional"))
    )
    (net (code "18") (name "/SDA2_ISO") (class "Default")
      (node (ref "J6") (pin "2") (pinfunction "2_2") (pintype "passive"))
      (node (ref "R23") (pin "1") (pinfunction "1_1") (pintype "passive"))
      (node (ref "U2") (pin "18") (pinfunction "SDA1_18") (pintype "bidirectional"))
    )
    (net (code "19") (name "/SD_CS") (class "Default")
      (node (ref "M1") (pin "10") (pinfunction "A5_10") (pintype "bidirectional"))
      (node (ref "U7") (pin "2") (pinfunction "1A_2") (pintype "input"))
    )
    (net (code "20") (name "/SD_MISO") (class "Default")
      (node (ref "J17") (pin "7") (pinfunction "D0_7") (pintype "passive"))
      (node (ref "M1") (pin "12") (pinfunction "MI_12") (pintype "passive"))
    )
    (net (code "21") (name "/SD_MOSI") (class "Default")
      (node (ref "M1") (pin "13") (pinfunction "MO_13") (pintype "passive"))
      (node (ref "U7") (pin "5") (pinfunction "2A_5") (pintype "input"))
    )
    (net (code "22") (name "/SD_SCK") (class "Default")
      (node (ref "M1") (pin "11") (pinfunction "SCK_11") (pintype "passive"))
      (node (ref "U7") (pin "9") (pinfunction "3A_9") (pintype "input"))
    )
    (net (code "23") (name "/SNS_EN1") (class "Default")
      (node (ref "M1") (pin "22") (pinfunction "D5_22") (pintype "bidirectional"))
      (node (ref "Q1") (pin "1") (pinfunction "G_1") (pintype "passive"))
      (node (ref "R1") (pin "1") (pinfunction "1_1") (pintype "passive"))
    )
    (net (code "24") (name "/SNS_EN2") (class "Default")
      (node (ref "M1") (pin "21") (pinfunction "D4_21") (pintype "bidirectional"))
      (node (ref "Q2") (pin "1") (pinfunction "G_1") (pintype "passive"))
      (node (ref "R2") (pin "1") (pinfunction "1_1") (pintype "passive"))
    )
    (net (code "25") (name "GND") (class "Default")
      (node (ref "C1") (pin "1") (pinfunction "1_1") (pintype "passive"))
      (node (ref "C10") (pin "2") (pinfunction "2_2") (pintype "passive"))
      (node (ref "C11") (pin "2") (pinfunction "2_2") (pintype "passive"))
      (node (ref "C2") (pin "2") (pinfunction "2_2") (pintype "passive"))
      (node (ref "C20") (pin "1") (pinfunction "1_1") (pintype "passive"))
      (node (ref "C22") (pin "1") (pinfunction "1_1") (pintype "passive"))
      (node (ref "C23") (pin "2") (pinfunction "2_2") (pintype "passive"))
      (node (ref "C25") (pin "1") (pinfunction "1_1") (pintype "passive"))
      (node (ref "C26") (pin "2") (pinfunction "2_2") (pintype "passive"))
      (node (ref "C27") (pin "2") (pinfunction "2_2") (pintype "passive"))
      (node (ref "C28") (pin "1") (pinfunction "1_1") (pintype "passive"))
      (node (ref "C29") (pin "2") (pinfunction "2_2") (pintype "passive"))
      (node (ref "C3") (pin "1") (pinfunction "1_1") (pintype "passive"))
      (node (ref "C30") (pin "1") (pinfunction "1_1") (pintype "passive"))
      (node (ref "C4") (pin "2") (pinfunction "2_2") (pintype "passive"))
      (node (ref "C5") (pin "1") (pinfunction "1_1") (pintype "passive"))
      (node (ref "C6") (pin "2") (pinfunction "2_2") (pintype "passive"))
      (node (ref "C7") (pin "1") (pinfunction "1_1") (pintype "passive"))
      (node (ref "C8") (pin "2") (pinfunction "2_2") (pintype "passive"))
      (node (ref "C9") (pin "1") (pinfunction "1_1") (pintype "passive"))
      (node (ref "J1") (pin "2") (pinfunction "2_2") (pintype "passive"))
      (node (ref "J11") (pin "2") (pinfunction "2_2") (pintype "passive"))
      (node (ref "J12") (pin "5") (pinfunction "5_5") (pintype "passive"))
      (node (ref "J13") (pin "4") (pinfunction "4_4") (pintype "passive"))
      (node (ref "J14") (pin "2") (pinfunction "2_2") (pintype "passive"))
      (node (ref "J15") (pin "4") (pinfunction "4_4") (pintype "passive"))
      (node (ref "J16") (pin "2") (pinfunction "2_2") (pintype "power_in"))
      (node (ref "J16") (pin "3") (pinfunction "3_3") (pintype "power_in"))
      (node (ref "J17") (pin "6") (pinfunction "VSS_6") (pintype "passive"))
      (node (ref "J17") (pin "9") (pinfunction "CD0(Body)_9") (pintype "passive"))
      (node (ref "J18") (pin "1") (pinfunction "1_1") (pintype "passive"))
      (node (ref "J19") (pin "1") (pinfunction "1_1") (pintype "passive"))
      (node (ref "J2") (pin "2") (pinfunction "2_2") (pintype "passive"))
      (node (ref "J20") (pin "1") (pinfunction "1_1") (pintype "passive"))
      (node (ref "J3") (pin "3") (pinfunction "3_3") (pintype "passive"))
      (node (ref "J4") (pin "1") (pinfunction "1_1") (pintype "passive"))
      (node (ref "M1") (pin "4") (pinfunction "GND_4") (pintype "power_in"))
      (node (ref "Q1") (pin "2") (pinfunction "S_2") (pintype "passive"))
      (node (ref "Q2") (pin "2") (pinfunction "S_2") (pintype "passive"))
      (node (ref "R11") (pin "1") (pinfunction "1_1") (pintype "passive"))
      (node (ref "R19") (pin "1") (pinfunction "1_1") (pintype "passive"))
      (node (ref "S1") (pin "3") (pintype "passive"))
      (node (ref "S1") (pin "6") (pintype "passive"))
      (node (ref "U1") (pin "1") (pinfunction "GNDP_1") (pintype "power_in"))
      (node (ref "U1") (pin "10") (pinfunction "GNDP_10") (pintype "power_in"))
      (node (ref "U1") (pin "5") (pinfunction "GNDP_5") (pintype "power_in"))
      (node (ref "U1") (pin "7") (pinfunction "GNDP_7") (pintype "power_in"))
      (node (ref "U2") (pin "1") (pinfunction "GNDP_1") (pintype "power_in"))
      (node (ref "U2") (pin "10") (pinfunction "GNDP_10") (pintype "power_in"))
      (node (ref "U2") (pin "5") (pinfunction "GNDP_5") (pintype "power_in"))
      (node (ref "U2") (pin "7") (pinfunction "GNDP_7") (pintype "power_in"))
      (node (ref "U3") (pin "2") (pinfunction "GND_2") (pintype "power_in"))
      (node (ref "U4") (pin "2") (pinfunction "GND_2") (pintype "power_in"))
      (node (ref "U5") (pin "2") (pinfunction "GND_2") (pintype "power_in"))
      (node (ref "U6") (pin "3") (pinfunction "GND_3") (pintype "power_in"))
      (node (ref "U7") (pin "7") (pinfunction "GND_7") (pintype "power_in"))
      (node (ref "U8") (pin "7") (pinfunction "GND_7") (pintype "power_in"))
      (node (ref "U9") (pin "1") (pinfunction "GND_1") (pintype "power_in"))
      (node (ref "U9") (pin "7") (pinfunction "GND_7") (pintype "power_in"))
    )
    (net (code "26") (name "GND_ISO1") (class "Default")
      (node (ref "C12") (pin "1") (pinfunction "1_1") (pintype "passive"))
      (node (ref "C13") (pin "2") (pinfunction "2_2") (pintype "passive"))
      (node (ref "C16") (pin "1") (pinfunction "1_1") (pintype "passive"))
      (node (ref "C17") (pin "2") (pinfunction "2_2") (pintype "passive"))
      (node (ref "J5") (pin "1") (pinfunction "1_1") (pintype "passive"))
      (node (ref "R14") (pin "1") (pinfunction "1_1") (pintype "passive"))
      (node (ref "R24") (pin "2") (pinfunction "2_2") (pintype "passive"))
      (node (ref "U1") (pin "11") (pinfunction "GNDISO_11") (pintype "power_in"))
      (node (ref "U1") (pin "14") (pinfunction "GNDISO_14") (pintype "power_in"))
      (node (ref "U1") (pin "16") (pinfunction "GNDISO_16") (pintype "power_in"))
      (node (ref "U1") (pin "20") (pinfunction "GNDISO_20") (pintype "power_in"))
    )
    (net (code "27") (name "GND_ISO2") (class "Default")
      (node (ref "C14") (pin "1") (pinfunction "1_1") (pintype "passive"))
      (node (ref "C15") (pin "2") (pinfunction "2_2") (pintype "passive"))
      (node (ref "C18") (pin "1") (pinfunction "1_1") (pintype "passive"))
      (node (ref "C19") (pin "2") (pinfunction "2_2") (pintype "passive"))
      (node (ref "J6") (pin "1") (pinfunction "1_1") (pintype "passive"))
      (node (ref "R17") (pin "1") (pinfunction "1_1") (pintype "passive"))
      (node (ref "R24") (pin "1") (pinfunction "1_1") (pintype "passive"))
      (node (ref "U2") (pin "11") (pinfunction "GNDISO_11") (pintype "power_in"))
      (node (ref "U2") (pin "14") (pinfunction "GNDISO_14") (pintype "power_in"))
      (node (ref "U2") (pin "16") (pinfunction "GNDISO_16") (pintype "power_in"))
      (node (ref "U2") (pin "20") (pinfunction "GNDISO_20") (pintype "power_in"))
    )
    (net (code "28") (name "Net-(D1-A)") (class "Default")
      (node (ref "D1") (pin "1") (pinfunction "A_1") (pintype "passive"))
      (node (ref "L1") (pin "2") (pinfunction "2_2") (pintype "passive"))
      (node (ref "U5") (pin "1") (pinfunction "SW_1") (pintype "passive"))
    )
    (net (code "29") (name "Net-(D2-A)") (class "Default")
      (node (ref "D2") (pin "1") (pinfunction "A_1") (pintype "passive"))
      (node (ref "J16") (pin "1") (pinfunction "1_1") (pintype "power_in"))
    )
    (net (code "30") (name "Net-(J7-Pad2)") (class "Default")
      (node (ref "J7") (pin "2") (pinfunction "2_2") (pintype "passive"))
      (node (ref "J9") (pin "1") (pinfunction "1_1") (pintype "passive"))
    )
    (net (code "31") (name "Net-(J7-Pad3)") (class "Default")
      (node (ref "J7") (pin "3") (pinfunction "3_3") (pintype "passive"))
      (node (ref "J9") (pin "2") (pinfunction "2_2") (pintype "passive"))
    )
    (net (code "32") (name "Net-(J10-Pad1)") (class "Default")
      (node (ref "J10") (pin "1") (pinfunction "1_1") (pintype "passive"))
      (node (ref "J8") (pin "2") (pinfunction "2_2") (pintype "passive"))
    )
    (net (code "33") (name "Net-(J10-Pad2)") (class "Default")
      (node (ref "J10") (pin "2") (pinfunction "2_2") (pintype "passive"))
      (node (ref "J8") (pin "3") (pinfunction "3_3") (pintype "passive"))
    )
    (net (code "34") (name "Net-(J17-CD{slash}D3)") (class "Default")
      (node (ref "J17") (pin "2") (pinfunction "CD/D3_2") (pintype "passive"))
      (node (ref "U7") (pin "3") (pinfunction "1Y_3") (pintype "output"))
    )
    (net (code "35") (name "Net-(J17-CLK)") (class "Default")
      (node (ref "J17") (pin "5") (pinfunction "CLK_5") (pintype "passive"))
      (node (ref "U7") (pin "8") (pinfunction "3Y_8") (pintype "output"))
    )
    (net (code "36") (name "Net-(J17-CMD)") (class "Default")
      (node (ref "J17") (pin "3") (pinfunction "CMD_3") (pintype "passive"))
      (node (ref "U7") (pin "6") (pinfunction "2Y_6") (pintype "output"))
    )
    (net (code "37") (name "Net-(M1-D7)") (class "Default")
      (node (ref "M1") (pin "24") (pinfunction "D7_24") (pintype "bidirectional"))
      (node (ref "R38") (pin "1") (pinfunction "1_1") (pintype "passive"))
      (node (ref "S1") (pin "2") (pintype "passive"))
      (node (ref "S1") (pin "5") (pintype "passive"))
    )
    (net (code "38") (name "Net-(M1-EN)") (class "Default")
      (node (ref "J11") (pin "1") (pinfunction "1_1") (pintype "passive"))
      (node (ref "M1") (pin "27") (pinfunction "EN_27") (pintype "input"))
    )
    (net (code "39") (name "Net-(M1-LI+)") (class "Default")
      (node (ref "J14") (pin "1") (pinfunction "1_1") (pintype "passive"))
      (node (ref "M1") (pin "28") (pinfunction "LI+_28") (pintype "power_in"))
    )
    (net (code "40") (name "Net-(M1-RX)") (class "Default")
      (node (ref "J13") (pin "3") (pinfunction "3_3") (pintype "passive"))
      (node (ref "M1") (pin "14") (pinfunction "RX_14") (pintype "passive"))
    )
    (net (code "41") (name "Net-(M1-TX)") (class "Default")
      (node (ref "J13") (pin "2") (pinfunction "2_2") (pintype "passive"))
      (node (ref "M1") (pin "15") (pinfunction "TX_15") (pintype "passive"))
    )
    (net (code "42") (name "Net-(Q1-D)") (class "Default")
      (node (ref "Q1") (pin "3") (pinfunction "D_3") (pintype "passive"))
      (node (ref "R7") (pin "1") (pinfunction "1_1") (pintype "passive"))
      (node (ref "U1") (pin "8") (pinfunction "PDIS_8") (pintype "input"))
    )
    (net (code "43") (name "Net-(Q2-D)") (class "Default")
      (node (ref "Q2") (pin "3") (pinfunction "D_3") (pintype "passive"))
      (node (ref "R8") (pin "1") (pinfunction "1_1") (pintype "passive"))
      (node (ref "U2") (pin "8") (pinfunction "PDIS_8") (pintype "input"))
    )
    (net (code "44") (name "Net-(R12-Pad1)") (class "Default")
      (node (ref "R12") (pin "1") (pinfunction "1_1") (pintype "passive"))
      (node (ref "R13") (pin "2") (pinfunction "2_2") (pintype "passive"))
    )
    (net (code "45") (name "Net-(R15-Pad1)") (class "Default")
      (node (ref "R15") (pin "1") (pinfunction "1_1") (pintype "passive"))
      (node (ref "R16") (pin "2") (pinfunction "2_2") (pintype "passive"))
    )
    (net (code "46") (name "Net-(U1-VSEL)") (class "Default")
      (node (ref "R13") (pin "1") (pinfunction "1_1") (pintype "passive"))
      (node (ref "R14") (pin "2") (pinfunction "2_2") (pintype "passive"))
      (node (ref "U1") (pin "13") (pinfunction "VSEL_13") (pintype "passive"))
    )
    (net (code "47") (name "Net-(U2-VSEL)") (class "Default")
      (node (ref "R16") (pin "1") (pinfunction "1_1") (pintype "passive"))
      (node (ref "R17") (pin "2") (pinfunction "2_2") (pintype "passive"))
      (node (ref "U2") (pin "13") (pinfunction "VSEL_13") (pintype "passive"))
    )
    (net (code "48") (name "Net-(U3-OUT)") (class "Default")
      (node (ref "U3") (pin "1") (pinfunction "OUT_1") (pintype "output"))
      (node (ref "U6") (pin "4") (pinfunction "AIN0_4") (pintype "input"))
    )
    (net (code "49") (name "Net-(U3-VIN-)") (class "Default")
      (node (ref "J1") (pin "1") (pinfunction "1_1") (pintype "passive"))
      (node (ref "R9") (pin "1") (pinfunction "1_1") (pintype "passive"))
      (node (ref "U3") (pin "5") (pinfunction "VIN-_5") (pintype "input"))
    )
    (net (code "50") (name "Net-(U4-OUT)") (class "Default")
      (node (ref "U4") (pin "1") (pinfunction "OUT_1") (pintype "output"))
      (node (ref "U6") (pin "5") (pinfunction "AIN1_5") (pintype "input"))
    )
    (net (code "51") (name "Net-(U4-VIN-)") (class "Default")
      (node (ref "J2") (pin "1") (pinfunction "1_1") (pintype "passive"))
      (node (ref "R10") (pin "1") (pinfunction "1_1") (pintype "passive"))
      (node (ref "U4") (pin "5") (pinfunction "VIN-_5") (pintype "input"))
    )
    (net (code "52") (name "Net-(U5-FB)") (class "Default")
      (node (ref "C21") (pin "1") (pinfunction "1_1") (pintype "passive"))
      (node (ref "R18") (pin "1") (pinfunction "1_1") (pintype "passive"))
      (node (ref "R19") (pin "2") (pinfunction "2_2") (pintype "passive"))
      (node (ref "U5") (pin "3") (pinfunction "FB_3") (pintype "input"))
    )
    (net (code "53") (name "Net-(U6-ADDR)") (class "Default")
      (node (ref "J4") (pin "2") (pinfunction "2_2") (pintype "passive"))
      (node (ref "U6") (pin "1") (pinfunction "ADDR_1") (pintype "input"))
    )
    (net (code "54") (name "Net-(U6-AIN2)") (class "Default")
      (node (ref "J3") (pin "1") (pinfunction "1_1") (pintype "passive"))
      (node (ref "U6") (pin "6") (pinfunction "AIN2_6") (pintype "input"))
    )
    (net (code "55") (name "Net-(U6-AIN3)") (class "Default")
      (node (ref "J3") (pin "2") (pinfunction "2_2") (pintype "passive"))
      (node (ref "U6") (pin "7") (pinfunction "AIN3_7") (pintype "input"))
    )
    (net (code "56") (name "Net-(U8-A0)") (class "Default")
      (node (ref "J20") (pin "2") (pinfunction "2_2") (pintype "passive"))
      (node (ref "U8") (pin "2") (pinfunction "A0_2") (pintype "input"))
    )
    (net (code "57") (name "Net-(U8-A1)") (class "Default")
      (node (ref "J19") (pin "2") (pinfunction "2_2") (pintype "passive"))
      (node (ref "U8") (pin "1") (pinfunction "A1_1") (pintype "input"))
    )
    (net (code "58") (name "Net-(U8-IN+)") (class "Default")
      (node (ref "C24") (pin "1") (pinfunction "1_1") (pintype "passive"))
      (node (ref "R32") (pin "1") (pinfunction "1_1") (pintype "passive"))
      (node (ref "U8") (pin "10") (pinfunction "IN+_10") (pintype "input"))
    )
    (net (code "59") (name "Net-(U8-IN-)") (class "Default")
      (node (ref "C24") (pin "2") (pinfunction "2_2") (pintype "passive"))
      (node (ref "R33") (pin "1") (pinfunction "1_1") (pintype "passive"))
      (node (ref "U8") (pin "9") (pinfunction "IN-_9") (pintype "input"))
    )
    (net (code "60") (name "Net-(U9-SDO)") (class "Default")
      (node (ref "J18") (pin "2") (pinfunction "2_2") (pintype "passive"))
      (node (ref "U9") (pin "5") (pinfunction "SDO_5") (pintype "output"))
    )
    (net (code "61") (name "unconnected-(FID1-Pad1)") (class "Default")
      (node (ref "FID1") (pin "1") (pinfunction "1_1") (pintype "passive"))
    )
    (net (code "62") (name "unconnected-(FID2-Pad1)") (class "Default")
      (node (ref "FID2") (pin "1") (pinfunction "1_1") (pintype "passive"))
    )
    (net (code "63") (name "unconnected-(FID3-Pad1)") (class "Default")
      (node (ref "FID3") (pin "1") (pinfunction "1_1") (pintype "passive"))
    )
    (net (code "64") (name "unconnected-(J17-CD1-Pad10)") (class "Default")
      (node (ref "J17") (pin "10") (pinfunction "CD1_10") (pintype "passive"))
    )
    (net (code "65") (name "unconnected-(J17-D1-Pad8)") (class "Default")
      (node (ref "J17") (pin "8") (pinfunction "D1_8") (pintype "passive"))
    )
    (net (code "66") (name "unconnected-(J17-D2-Pad1)") (class "Default")
      (node (ref "J17") (pin "1") (pinfunction "D2_1") (pintype "passive"))
    )
    (net (code "67") (name "unconnected-(M1-A2-Pad7)") (class "Default")
      (node (ref "M1") (pin "7") (pinfunction "A2_7") (pintype "bidirectional"))
    )
    (net (code "68") (name "unconnected-(M1-A3-Pad8)") (class "Default")
      (node (ref "M1") (pin "8") (pinfunction "A3_8") (pintype "bidirectional"))
    )
    (net (code "69") (name "unconnected-(M1-A4-Pad9)") (class "Default")
      (node (ref "M1") (pin "9") (pinfunction "A4_9") (pintype "bidirectional"))
    )
    (net (code "70") (name "unconnected-(M1-NC-Pad16)") (class "Default")
      (node (ref "M1") (pin "16") (pinfunction "NC_16") (pintype "passive"))
    )
    (net (code "71") (name "unconnected-(M1-~{MD}-Pad3)") (class "Default")
      (node (ref "M1") (pin "3") (pinfunction "~{MD}_3") (pintype "input+no_connect"))
    )
    (net (code "72") (name "unconnected-(M1-~{RST}-Pad1)") (class "Default")
      (node (ref "M1") (pin "1") (pinfunction "~{RST}_1") (pintype "input+no_connect"))
    )
    (net (code "73") (name "unconnected-(S1-Pad1)") (class "Default")
      (node (ref "S1") (pin "1") (pintype "passive"))
    )
    (net (code "74") (name "unconnected-(S1-Pad4)") (class "Default")
      (node (ref "S1") (pin "4") (pintype "passive"))
    )
    (net (code "75") (name "unconnected-(U1-NC-Pad6)") (class "Default")
      (node (ref "U1") (pin "6") (pinfunction "NC_6") (pintype "passive"))
    )
    (net (code "76") (name "unconnected-(U1-NC-Pad15)") (class "Default")
      (node (ref "U1") (pin "15") (pinfunction "NC_15") (pintype "passive"))
    )
    (net (code "77") (name "unconnected-(U2-NC-Pad6)") (class "Default")
      (node (ref "U2") (pin "6") (pinfunction "NC_6") (pintype "passive"))
    )
    (net (code "78") (name "unconnected-(U2-NC-Pad15)") (class "Default")
      (node (ref "U2") (pin "15") (pinfunction "NC_15") (pintype "passive"))
    )
    (net (code "79") (name "unconnected-(U7D-4Y-Pad11)") (class "Default")
      (node (ref "U7") (pin "11") (pinfunction "4Y_11") (pintype "output"))
    )
  )
)
